# board_design.net
KiCad netlist of a schematic drawn in EAGLE
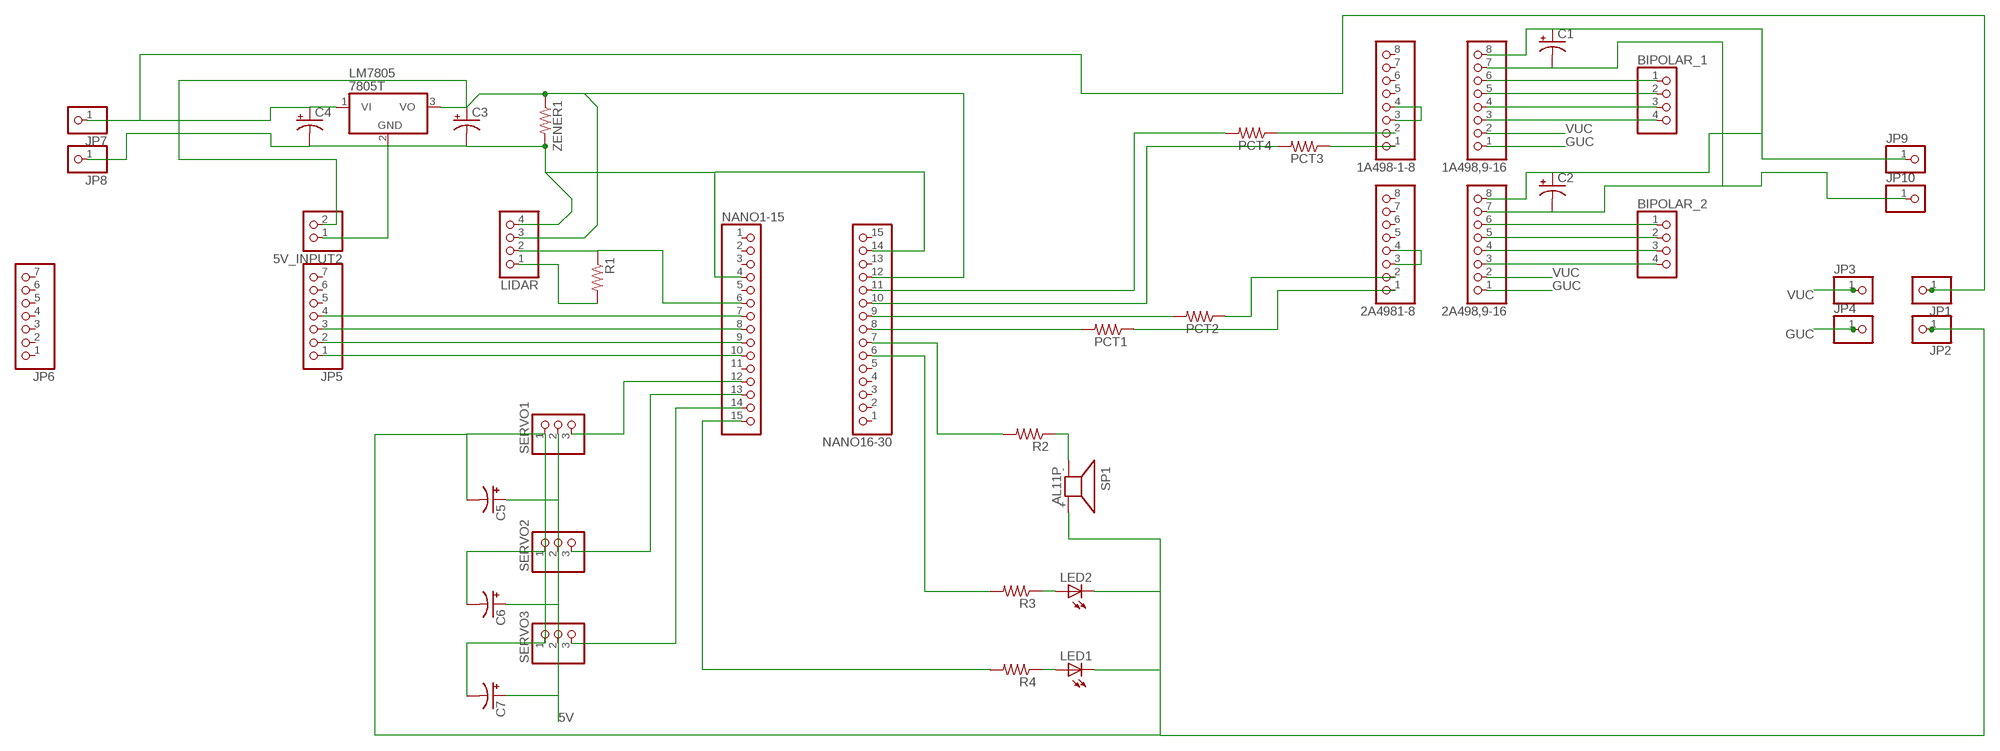
[diagram p0: schematic, sheet 1]

(export (version "E")
  (design (tool "Eeschema 10.0.6"))
  (components
    (comp (ref "1A498,9-16")
      (value "PINHD-1X8")
      (footprint "eagle-import:1X08")
      (libsource (lib "eagle-import") (part "PINHD-1X8"))
    )
    (comp (ref "1A498-1-8")
      (value "PINHD-1X8")
      (footprint "eagle-import:1X08")
      (libsource (lib "eagle-import") (part "PINHD-1X8"))
    )
    (comp (ref "2A498,9-16")
      (value "PINHD-1X8")
      (footprint "eagle-import:1X08")
      (libsource (lib "eagle-import") (part "PINHD-1X8"))
    )
    (comp (ref "2A4981-8")
      (value "PINHD-1X8")
      (footprint "eagle-import:1X08")
      (libsource (lib "eagle-import") (part "PINHD-1X8"))
    )
    (comp (ref "5V_INPUT2")
      (value "PINHD-1X2")
      (footprint "eagle-import:1X02")
      (libsource (lib "eagle-import") (part "PINHD-1X2"))
    )
    (comp (ref "BIPOLAR_1")
      (value "PINHD-1X4")
      (footprint "eagle-import:1X04")
      (libsource (lib "eagle-import") (part "PINHD-1X4"))
    )
    (comp (ref "BIPOLAR_2")
      (value "PINHD-1X4")
      (footprint "eagle-import:1X04")
      (libsource (lib "eagle-import") (part "PINHD-1X4"))
    )
    (comp (ref "C1")
      (value "CPOL-USE2.5-7")
      (footprint "eagle-import:E2,5-7")
      (libsource (lib "eagle-import") (part "CPOL-USE2.5-7"))
    )
    (comp (ref "C2")
      (value "CPOL-USE2.5-7")
      (footprint "eagle-import:E2,5-7")
      (libsource (lib "eagle-import") (part "CPOL-USE2.5-7"))
    )
    (comp (ref "C3")
      (value "CPOL-USE2.5-7")
      (footprint "eagle-import:E2,5-7")
      (libsource (lib "eagle-import") (part "CPOL-USE2.5-7"))
    )
    (comp (ref "C4")
      (value "CPOL-USE2.5-7")
      (footprint "eagle-import:E2,5-7")
      (libsource (lib "eagle-import") (part "CPOL-USE2.5-7"))
    )
    (comp (ref "C5")
      (value "CPOL-USE2.5-7")
      (footprint "eagle-import:E2,5-7")
      (libsource (lib "eagle-import") (part "CPOL-USE2.5-7"))
    )
    (comp (ref "C6")
      (value "CPOL-USE2.5-7")
      (footprint "eagle-import:E2,5-7")
      (libsource (lib "eagle-import") (part "CPOL-USE2.5-7"))
    )
    (comp (ref "C7")
      (value "CPOL-USE2.5-7")
      (footprint "eagle-import:E2,5-7")
      (libsource (lib "eagle-import") (part "CPOL-USE2.5-7"))
    )
    (comp (ref "JP1")
      (value "PINHD-1X1")
      (footprint "eagle-import:1X01")
      (libsource (lib "eagle-import") (part "PINHD-1X1"))
    )
    (comp (ref "JP2")
      (value "PINHD-1X1")
      (footprint "eagle-import:1X01")
      (libsource (lib "eagle-import") (part "PINHD-1X1"))
    )
    (comp (ref "JP3")
      (value "PINHD-1X1")
      (footprint "eagle-import:1X01")
      (libsource (lib "eagle-import") (part "PINHD-1X1"))
    )
    (comp (ref "JP4")
      (value "PINHD-1X1")
      (footprint "eagle-import:1X01")
      (libsource (lib "eagle-import") (part "PINHD-1X1"))
    )
    (comp (ref "JP5")
      (value "PINHD-1X7")
      (footprint "eagle-import:1X07")
      (libsource (lib "eagle-import") (part "PINHD-1X7"))
    )
    (comp (ref "JP6")
      (value "PINHD-1X7")
      (footprint "eagle-import:1X07")
      (libsource (lib "eagle-import") (part "PINHD-1X7"))
    )
    (comp (ref "JP7")
      (value "PINHD-1X1")
      (footprint "eagle-import:1X01")
      (libsource (lib "eagle-import") (part "PINHD-1X1"))
    )
    (comp (ref "JP8")
      (value "PINHD-1X1")
      (footprint "eagle-import:1X01")
      (libsource (lib "eagle-import") (part "PINHD-1X1"))
    )
    (comp (ref "JP9")
      (value "PINHD-1X1")
      (footprint "eagle-import:1X01")
      (libsource (lib "eagle-import") (part "PINHD-1X1"))
    )
    (comp (ref "JP10")
      (value "PINHD-1X1")
      (footprint "eagle-import:1X01")
      (libsource (lib "eagle-import") (part "PINHD-1X1"))
    )
    (comp (ref "LED1")
      (value "LED5MM")
      (footprint "eagle-import:LED5MM")
      (libsource (lib "eagle-import") (part "LED5MM"))
    )
    (comp (ref "LED2")
      (value "LED5MM")
      (footprint "eagle-import:LED5MM")
      (libsource (lib "eagle-import") (part "LED5MM"))
    )
    (comp (ref "LIDAR")
      (value "PINHD-1X4")
      (footprint "eagle-import:1X04")
      (libsource (lib "eagle-import") (part "PINHD-1X4"))
    )
    (comp (ref "LM7805")
      (value "7805T")
      (footprint "eagle-import:TO220H")
      (libsource (lib "eagle-import") (part "78T05"))
    )
    (comp (ref "NANO1-15")
      (value "PINHD-1X15")
      (footprint "eagle-import:1X15")
      (libsource (lib "eagle-import") (part "PINHD-1X15"))
    )
    (comp (ref "NANO16-30")
      (value "PINHD-1X15")
      (footprint "eagle-import:1X15")
      (libsource (lib "eagle-import") (part "PINHD-1X15"))
    )
    (comp (ref "PCT1")
      (value "R-US_0207/10")
      (footprint "eagle-import:0207_10")
      (libsource (lib "eagle-import") (part "R-US_0207/10"))
    )
    (comp (ref "PCT2")
      (value "R-US_0207/10")
      (footprint "eagle-import:0207_10")
      (libsource (lib "eagle-import") (part "R-US_0207/10"))
    )
    (comp (ref "PCT3")
      (value "R-US_0207/10")
      (footprint "eagle-import:0207_10")
      (libsource (lib "eagle-import") (part "R-US_0207/10"))
    )
    (comp (ref "PCT4")
      (value "R-US_0207/10")
      (footprint "eagle-import:0207_10")
      (libsource (lib "eagle-import") (part "R-US_0207/10"))
    )
    (comp (ref "R1")
      (value "R-US_0207/10")
      (footprint "eagle-import:0207_10")
      (libsource (lib "eagle-import") (part "R-US_0207/10"))
    )
    (comp (ref "R2")
      (value "R-US_0207/10")
      (footprint "eagle-import:0207_10")
      (libsource (lib "eagle-import") (part "R-US_0207/10"))
    )
    (comp (ref "R3")
      (value "R-US_0207/10")
      (footprint "eagle-import:0207_10")
      (libsource (lib "eagle-import") (part "R-US_0207/10"))
    )
    (comp (ref "R4")
      (value "R-US_0207/10")
      (footprint "eagle-import:0207_10")
      (libsource (lib "eagle-import") (part "R-US_0207/10"))
    )
    (comp (ref "SERVO1")
      (value "PINHD-1X3")
      (footprint "eagle-import:1X03")
      (libsource (lib "eagle-import") (part "PINHD-1X3"))
    )
    (comp (ref "SERVO2")
      (value "PINHD-1X3")
      (footprint "eagle-import:1X03")
      (libsource (lib "eagle-import") (part "PINHD-1X3"))
    )
    (comp (ref "SERVO3")
      (value "PINHD-1X3")
      (footprint "eagle-import:1X03")
      (libsource (lib "eagle-import") (part "PINHD-1X3"))
    )
    (comp (ref "SP1")
      (value "AL11P")
      (footprint "eagle-import:AL11P")
      (libsource (lib "eagle-import") (part "AL11P"))
    )
    (comp (ref "ZENER1")
      (value "R-US_0207/10")
      (footprint "eagle-import:0207_10")
      (libsource (lib "eagle-import") (part "R-US_0207/10"))
    )
  )
  (nets
    (net (code "1") (name "/5V") (class "Default")
      (node (ref "C4") (pin "+") (pinfunction "+_+") (pintype "passive"))
      (node (ref "C5") (pin "+") (pinfunction "+_+") (pintype "passive"))
      (node (ref "C6") (pin "+") (pinfunction "+_+") (pintype "passive"))
      (node (ref "C7") (pin "+") (pinfunction "+_+") (pintype "passive"))
      (node (ref "JP1") (pin "1") (pinfunction "1_1") (pintype "passive"))
      (node (ref "JP7") (pin "1") (pinfunction "1_1") (pintype "passive"))
      (node (ref "LM7805") (pin "1") (pinfunction "VI_1") (pintype "input"))
      (node (ref "SERVO1") (pin "2") (pinfunction "2_2") (pintype "passive"))
      (node (ref "SERVO2") (pin "2") (pinfunction "2_2") (pintype "passive"))
      (node (ref "SERVO3") (pin "2") (pinfunction "2_2") (pintype "passive"))
    )
    (net (code "2") (name "/GUC") (class "Default")
      (node (ref "1A498,9-16") (pin "1") (pinfunction "1_1") (pintype "passive"))
      (node (ref "2A498,9-16") (pin "1") (pinfunction "1_1") (pintype "passive"))
      (node (ref "JP4") (pin "1") (pinfunction "1_1") (pintype "passive"))
    )
    (net (code "3") (name "/VUC") (class "Default")
      (node (ref "1A498,9-16") (pin "2") (pinfunction "2_2") (pintype "passive"))
      (node (ref "2A498,9-16") (pin "2") (pinfunction "2_2") (pintype "passive"))
      (node (ref "JP3") (pin "1") (pinfunction "1_1") (pintype "passive"))
    )
    (net (code "4") (name "Net-(1A498,9-16-Pad3)") (class "Default")
      (node (ref "1A498,9-16") (pin "3") (pinfunction "3_3") (pintype "passive"))
      (node (ref "BIPOLAR_1") (pin "4") (pinfunction "4_4") (pintype "passive"))
    )
    (net (code "5") (name "Net-(1A498,9-16-Pad4)") (class "Default")
      (node (ref "1A498,9-16") (pin "4") (pinfunction "4_4") (pintype "passive"))
      (node (ref "BIPOLAR_1") (pin "3") (pinfunction "3_3") (pintype "passive"))
    )
    (net (code "6") (name "Net-(1A498,9-16-Pad5)") (class "Default")
      (node (ref "1A498,9-16") (pin "5") (pinfunction "5_5") (pintype "passive"))
      (node (ref "BIPOLAR_1") (pin "2") (pinfunction "2_2") (pintype "passive"))
    )
    (net (code "7") (name "Net-(1A498,9-16-Pad6)") (class "Default")
      (node (ref "1A498,9-16") (pin "6") (pinfunction "6_6") (pintype "passive"))
      (node (ref "BIPOLAR_1") (pin "1") (pinfunction "1_1") (pintype "passive"))
    )
    (net (code "8") (name "Net-(1A498,9-16-Pad7)") (class "Default")
      (node (ref "1A498,9-16") (pin "7") (pinfunction "7_7") (pintype "passive"))
      (node (ref "2A498,9-16") (pin "7") (pinfunction "7_7") (pintype "passive"))
      (node (ref "C1") (pin "-") (pinfunction "-_-") (pintype "passive"))
      (node (ref "C2") (pin "-") (pinfunction "-_-") (pintype "passive"))
      (node (ref "JP10") (pin "1") (pinfunction "1_1") (pintype "passive"))
    )
    (net (code "9") (name "Net-(1A498,9-16-Pad8)") (class "Default")
      (node (ref "1A498,9-16") (pin "8") (pinfunction "8_8") (pintype "passive"))
      (node (ref "2A498,9-16") (pin "8") (pinfunction "8_8") (pintype "passive"))
      (node (ref "C1") (pin "+") (pinfunction "+_+") (pintype "passive"))
      (node (ref "C2") (pin "+") (pinfunction "+_+") (pintype "passive"))
      (node (ref "JP9") (pin "1") (pinfunction "1_1") (pintype "passive"))
    )
    (net (code "10") (name "Net-(1A498-1-8-Pad1)") (class "Default")
      (node (ref "1A498-1-8") (pin "1") (pinfunction "1_1") (pintype "passive"))
      (node (ref "PCT3") (pin "1") (pinfunction "1_1") (pintype "passive"))
    )
    (net (code "11") (name "Net-(1A498-1-8-Pad2)") (class "Default")
      (node (ref "1A498-1-8") (pin "2") (pinfunction "2_2") (pintype "passive"))
      (node (ref "PCT4") (pin "1") (pinfunction "1_1") (pintype "passive"))
    )
    (net (code "12") (name "Net-(1A498-1-8-Pad3)") (class "Default")
      (node (ref "1A498-1-8") (pin "3") (pinfunction "3_3") (pintype "passive"))
      (node (ref "1A498-1-8") (pin "4") (pinfunction "4_4") (pintype "passive"))
    )
    (net (code "13") (name "Net-(2A498,9-16-Pad3)") (class "Default")
      (node (ref "2A498,9-16") (pin "3") (pinfunction "3_3") (pintype "passive"))
      (node (ref "BIPOLAR_2") (pin "4") (pinfunction "4_4") (pintype "passive"))
    )
    (net (code "14") (name "Net-(2A498,9-16-Pad4)") (class "Default")
      (node (ref "2A498,9-16") (pin "4") (pinfunction "4_4") (pintype "passive"))
      (node (ref "BIPOLAR_2") (pin "3") (pinfunction "3_3") (pintype "passive"))
    )
    (net (code "15") (name "Net-(2A498,9-16-Pad5)") (class "Default")
      (node (ref "2A498,9-16") (pin "5") (pinfunction "5_5") (pintype "passive"))
      (node (ref "BIPOLAR_2") (pin "2") (pinfunction "2_2") (pintype "passive"))
    )
    (net (code "16") (name "Net-(2A498,9-16-Pad6)") (class "Default")
      (node (ref "2A498,9-16") (pin "6") (pinfunction "6_6") (pintype "passive"))
      (node (ref "BIPOLAR_2") (pin "1") (pinfunction "1_1") (pintype "passive"))
    )
    (net (code "17") (name "Net-(2A4981-8-Pad1)") (class "Default")
      (node (ref "2A4981-8") (pin "1") (pinfunction "1_1") (pintype "passive"))
      (node (ref "PCT1") (pin "1") (pinfunction "1_1") (pintype "passive"))
    )
    (net (code "18") (name "Net-(2A4981-8-Pad2)") (class "Default")
      (node (ref "2A4981-8") (pin "2") (pinfunction "2_2") (pintype "passive"))
      (node (ref "PCT2") (pin "1") (pinfunction "1_1") (pintype "passive"))
    )
    (net (code "19") (name "Net-(2A4981-8-Pad3)") (class "Default")
      (node (ref "2A4981-8") (pin "3") (pinfunction "3_3") (pintype "passive"))
      (node (ref "2A4981-8") (pin "4") (pinfunction "4_4") (pintype "passive"))
    )
    (net (code "20") (name "Net-(JP5-Pad1)") (class "Default")
      (node (ref "JP5") (pin "1") (pinfunction "1_1") (pintype "passive"))
      (node (ref "NANO1-15") (pin "10") (pinfunction "10_10") (pintype "passive"))
    )
    (net (code "21") (name "Net-(JP5-Pad2)") (class "Default")
      (node (ref "JP5") (pin "2") (pinfunction "2_2") (pintype "passive"))
      (node (ref "NANO1-15") (pin "9") (pinfunction "9_9") (pintype "passive"))
    )
    (net (code "22") (name "Net-(JP5-Pad3)") (class "Default")
      (node (ref "JP5") (pin "3") (pinfunction "3_3") (pintype "passive"))
      (node (ref "NANO1-15") (pin "8") (pinfunction "8_8") (pintype "passive"))
    )
    (net (code "23") (name "Net-(JP5-Pad4)") (class "Default")
      (node (ref "JP5") (pin "4") (pinfunction "4_4") (pintype "passive"))
      (node (ref "NANO1-15") (pin "7") (pinfunction "7_7") (pintype "passive"))
    )
    (net (code "24") (name "Net-(LED1-C)") (class "Default")
      (node (ref "C5") (pin "-") (pinfunction "-_-") (pintype "passive"))
      (node (ref "C6") (pin "-") (pinfunction "-_-") (pintype "passive"))
      (node (ref "C7") (pin "-") (pinfunction "-_-") (pintype "passive"))
      (node (ref "JP2") (pin "1") (pinfunction "1_1") (pintype "passive"))
      (node (ref "LED1") (pin "K") (pinfunction "C_K") (pintype "passive"))
      (node (ref "LED2") (pin "K") (pinfunction "C_K") (pintype "passive"))
      (node (ref "SERVO1") (pin "1") (pinfunction "1_1") (pintype "passive"))
      (node (ref "SERVO2") (pin "1") (pinfunction "1_1") (pintype "passive"))
      (node (ref "SERVO3") (pin "1") (pinfunction "1_1") (pintype "passive"))
      (node (ref "SP1") (pin "+") (pinfunction "2_+") (pintype "passive"))
    )
    (net (code "25") (name "Net-(LED1-PadA)") (class "Default")
      (node (ref "LED1") (pin "A") (pinfunction "A_A") (pintype "passive"))
      (node (ref "R4") (pin "1") (pinfunction "1_1") (pintype "passive"))
    )
    (net (code "26") (name "Net-(LED2-PadA)") (class "Default")
      (node (ref "LED2") (pin "A") (pinfunction "A_A") (pintype "passive"))
      (node (ref "R3") (pin "1") (pinfunction "1_1") (pintype "passive"))
    )
    (net (code "27") (name "Net-(LIDAR-Pad1)") (class "Default")
      (node (ref "LIDAR") (pin "1") (pinfunction "1_1") (pintype "passive"))
      (node (ref "R1") (pin "2") (pinfunction "2_2") (pintype "passive"))
    )
    (net (code "28") (name "Net-(LIDAR-Pad2)") (class "Default")
      (node (ref "LIDAR") (pin "2") (pinfunction "2_2") (pintype "passive"))
      (node (ref "NANO1-15") (pin "6") (pinfunction "6_6") (pintype "passive"))
      (node (ref "R1") (pin "1") (pinfunction "1_1") (pintype "passive"))
    )
    (net (code "29") (name "Net-(LM7805-GND)") (class "Default")
      (node (ref "5V_INPUT2") (pin "1") (pinfunction "1_1") (pintype "passive"))
      (node (ref "C3") (pin "-") (pinfunction "-_-") (pintype "passive"))
      (node (ref "C4") (pin "-") (pinfunction "-_-") (pintype "passive"))
      (node (ref "JP8") (pin "1") (pinfunction "1_1") (pintype "passive"))
      (node (ref "LIDAR") (pin "4") (pinfunction "4_4") (pintype "passive"))
      (node (ref "LM7805") (pin "2") (pinfunction "GND_2") (pintype "passive"))
      (node (ref "NANO1-15") (pin "4") (pinfunction "4_4") (pintype "passive"))
      (node (ref "NANO16-30") (pin "14") (pinfunction "14_14") (pintype "passive"))
      (node (ref "ZENER1") (pin "2") (pinfunction "2_2") (pintype "passive"))
    )
    (net (code "30") (name "Net-(LM7805-VO)") (class "Default")
      (node (ref "5V_INPUT2") (pin "2") (pinfunction "2_2") (pintype "passive"))
      (node (ref "C3") (pin "+") (pinfunction "+_+") (pintype "passive"))
      (node (ref "LIDAR") (pin "3") (pinfunction "3_3") (pintype "passive"))
      (node (ref "LM7805") (pin "3") (pinfunction "VO_3") (pintype "passive"))
      (node (ref "NANO16-30") (pin "12") (pinfunction "12_12") (pintype "passive"))
      (node (ref "ZENER1") (pin "1") (pinfunction "1_1") (pintype "passive"))
    )
    (net (code "31") (name "Net-(NANO1-15-Pad12)") (class "Default")
      (node (ref "NANO1-15") (pin "12") (pinfunction "12_12") (pintype "passive"))
      (node (ref "SERVO1") (pin "3") (pinfunction "3_3") (pintype "passive"))
    )
    (net (code "32") (name "Net-(NANO1-15-Pad13)") (class "Default")
      (node (ref "NANO1-15") (pin "13") (pinfunction "13_13") (pintype "passive"))
      (node (ref "SERVO2") (pin "3") (pinfunction "3_3") (pintype "passive"))
    )
    (net (code "33") (name "Net-(NANO1-15-Pad14)") (class "Default")
      (node (ref "NANO1-15") (pin "14") (pinfunction "14_14") (pintype "passive"))
      (node (ref "SERVO3") (pin "3") (pinfunction "3_3") (pintype "passive"))
    )
    (net (code "34") (name "Net-(NANO1-15-Pad15)") (class "Default")
      (node (ref "NANO1-15") (pin "15") (pinfunction "15_15") (pintype "passive"))
      (node (ref "R4") (pin "2") (pinfunction "2_2") (pintype "passive"))
    )
    (net (code "35") (name "Net-(NANO16-30-Pad6)") (class "Default")
      (node (ref "NANO16-30") (pin "6") (pinfunction "6_6") (pintype "passive"))
      (node (ref "R3") (pin "2") (pinfunction "2_2") (pintype "passive"))
    )
    (net (code "36") (name "Net-(NANO16-30-Pad7)") (class "Default")
      (node (ref "NANO16-30") (pin "7") (pinfunction "7_7") (pintype "passive"))
      (node (ref "R2") (pin "2") (pinfunction "2_2") (pintype "passive"))
    )
    (net (code "37") (name "Net-(NANO16-30-Pad8)") (class "Default")
      (node (ref "NANO16-30") (pin "8") (pinfunction "8_8") (pintype "passive"))
      (node (ref "PCT1") (pin "2") (pinfunction "2_2") (pintype "passive"))
    )
    (net (code "38") (name "Net-(NANO16-30-Pad9)") (class "Default")
      (node (ref "NANO16-30") (pin "9") (pinfunction "9_9") (pintype "passive"))
      (node (ref "PCT2") (pin "2") (pinfunction "2_2") (pintype "passive"))
    )
    (net (code "39") (name "Net-(NANO16-30-Pad10)") (class "Default")
      (node (ref "NANO16-30") (pin "10") (pinfunction "10_10") (pintype "passive"))
      (node (ref "PCT3") (pin "2") (pinfunction "2_2") (pintype "passive"))
    )
    (net (code "40") (name "Net-(NANO16-30-Pad11)") (class "Default")
      (node (ref "NANO16-30") (pin "11") (pinfunction "11_11") (pintype "passive"))
      (node (ref "PCT4") (pin "2") (pinfunction "2_2") (pintype "passive"))
    )
    (net (code "41") (name "Net-(SP1-1)") (class "Default")
      (node (ref "R2") (pin "1") (pinfunction "1_1") (pintype "passive"))
      (node (ref "SP1") (pin "-") (pinfunction "1_-") (pintype "passive"))
    )
    (net (code "42") (name "unconnected-(1A498-1-8-Pad5)") (class "Default")
      (node (ref "1A498-1-8") (pin "5") (pinfunction "5_5") (pintype "passive"))
    )
    (net (code "43") (name "unconnected-(1A498-1-8-Pad6)") (class "Default")
      (node (ref "1A498-1-8") (pin "6") (pinfunction "6_6") (pintype "passive"))
    )
    (net (code "44") (name "unconnected-(1A498-1-8-Pad7)") (class "Default")
      (node (ref "1A498-1-8") (pin "7") (pinfunction "7_7") (pintype "passive"))
    )
    (net (code "45") (name "unconnected-(1A498-1-8-Pad8)") (class "Default")
      (node (ref "1A498-1-8") (pin "8") (pinfunction "8_8") (pintype "passive"))
    )
    (net (code "46") (name "unconnected-(2A4981-8-Pad5)") (class "Default")
      (node (ref "2A4981-8") (pin "5") (pinfunction "5_5") (pintype "passive"))
    )
    (net (code "47") (name "unconnected-(2A4981-8-Pad6)") (class "Default")
      (node (ref "2A4981-8") (pin "6") (pinfunction "6_6") (pintype "passive"))
    )
    (net (code "48") (name "unconnected-(2A4981-8-Pad7)") (class "Default")
      (node (ref "2A4981-8") (pin "7") (pinfunction "7_7") (pintype "passive"))
    )
    (net (code "49") (name "unconnected-(2A4981-8-Pad8)") (class "Default")
      (node (ref "2A4981-8") (pin "8") (pinfunction "8_8") (pintype "passive"))
    )
    (net (code "50") (name "unconnected-(JP5-Pad5)") (class "Default")
      (node (ref "JP5") (pin "5") (pinfunction "5_5") (pintype "passive"))
    )
    (net (code "51") (name "unconnected-(JP5-Pad6)") (class "Default")
      (node (ref "JP5") (pin "6") (pinfunction "6_6") (pintype "passive"))
    )
    (net (code "52") (name "unconnected-(JP5-Pad7)") (class "Default")
      (node (ref "JP5") (pin "7") (pinfunction "7_7") (pintype "passive"))
    )
    (net (code "53") (name "unconnected-(JP6-Pad1)") (class "Default")
      (node (ref "JP6") (pin "1") (pinfunction "1_1") (pintype "passive"))
    )
    (net (code "54") (name "unconnected-(JP6-Pad2)") (class "Default")
      (node (ref "JP6") (pin "2") (pinfunction "2_2") (pintype "passive"))
    )
    (net (code "55") (name "unconnected-(JP6-Pad3)") (class "Default")
      (node (ref "JP6") (pin "3") (pinfunction "3_3") (pintype "passive"))
    )
    (net (code "56") (name "unconnected-(JP6-Pad4)") (class "Default")
      (node (ref "JP6") (pin "4") (pinfunction "4_4") (pintype "passive"))
    )
    (net (code "57") (name "unconnected-(JP6-Pad5)") (class "Default")
      (node (ref "JP6") (pin "5") (pinfunction "5_5") (pintype "passive"))
    )
    (net (code "58") (name "unconnected-(JP6-Pad6)") (class "Default")
      (node (ref "JP6") (pin "6") (pinfunction "6_6") (pintype "passive"))
    )
    (net (code "59") (name "unconnected-(JP6-Pad7)") (class "Default")
      (node (ref "JP6") (pin "7") (pinfunction "7_7") (pintype "passive"))
    )
    (net (code "60") (name "unconnected-(NANO1-15-Pad1)") (class "Default")
      (node (ref "NANO1-15") (pin "1") (pinfunction "1_1") (pintype "passive"))
    )
    (net (code "61") (name "unconnected-(NANO1-15-Pad2)") (class "Default")
      (node (ref "NANO1-15") (pin "2") (pinfunction "2_2") (pintype "passive"))
    )
    (net (code "62") (name "unconnected-(NANO1-15-Pad3)") (class "Default")
      (node (ref "NANO1-15") (pin "3") (pinfunction "3_3") (pintype "passive"))
    )
    (net (code "63") (name "unconnected-(NANO1-15-Pad5)") (class "Default")
      (node (ref "NANO1-15") (pin "5") (pinfunction "5_5") (pintype "passive"))
    )
    (net (code "64") (name "unconnected-(NANO1-15-Pad11)") (class "Default")
      (node (ref "NANO1-15") (pin "11") (pinfunction "11_11") (pintype "passive"))
    )
    (net (code "65") (name "unconnected-(NANO16-30-Pad1)") (class "Default")
      (node (ref "NANO16-30") (pin "1") (pinfunction "1_1") (pintype "passive"))
    )
    (net (code "66") (name "unconnected-(NANO16-30-Pad2)") (class "Default")
      (node (ref "NANO16-30") (pin "2") (pinfunction "2_2") (pintype "passive"))
    )
    (net (code "67") (name "unconnected-(NANO16-30-Pad3)") (class "Default")
      (node (ref "NANO16-30") (pin "3") (pinfunction "3_3") (pintype "passive"))
    )
    (net (code "68") (name "unconnected-(NANO16-30-Pad4)") (class "Default")
      (node (ref "NANO16-30") (pin "4") (pinfunction "4_4") (pintype "passive"))
    )
    (net (code "69") (name "unconnected-(NANO16-30-Pad5)") (class "Default")
      (node (ref "NANO16-30") (pin "5") (pinfunction "5_5") (pintype "passive"))
    )
    (net (code "70") (name "unconnected-(NANO16-30-Pad13)") (class "Default")
      (node (ref "NANO16-30") (pin "13") (pinfunction "13_13") (pintype "passive"))
    )
    (net (code "71") (name "unconnected-(NANO16-30-Pad15)") (class "Default")
      (node (ref "NANO16-30") (pin "15") (pinfunction "15_15") (pintype "passive"))
    )
  )
)
